# Inverter.net
KiCad netlist of a schematic drawn in Altium Designer
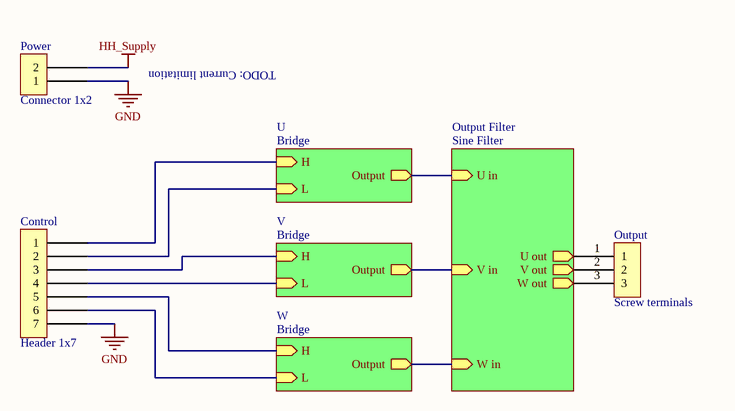
[diagram p0: Inverter.SchDoc]

(export (version "E")
  (design (tool "Eeschema 10.0.6"))
  (components
    (comp (ref "Control")
      (value "Header 1x7")
      (footprint "Header 1x7")
      (libsource (lib "Headers") (part "Header 1x7"))
    )
    (comp (ref "Output")
      (value "Screw terminals")
      (footprint "DG301-5.0-03")
      (libsource (lib "Headers") (part "Header 1x3"))
    )
    (comp (ref "Power")
      (value "Connector 1x2")
      (footprint "DG301-5.0-02")
      (libsource (lib "Headers") (part "Header 2x1"))
    )
  )
  (nets
    (net (code "1") (name "/H") (class "Default")
      (node (ref "Control") (pin "5") (pinfunction "5_5") (pintype "passive"))
    )
    (net (code "2") (name "/H_1") (class "Default")
      (node (ref "Control") (pin "1") (pinfunction "1_1") (pintype "passive"))
    )
    (net (code "3") (name "/H_2") (class "Default")
      (node (ref "Control") (pin "3") (pinfunction "3_3") (pintype "passive"))
    )
    (net (code "4") (name "/L") (class "Default")
      (node (ref "Control") (pin "4") (pinfunction "4_4") (pintype "passive"))
    )
    (net (code "5") (name "/L_1") (class "Default")
      (node (ref "Control") (pin "2") (pinfunction "2_2") (pintype "passive"))
    )
    (net (code "6") (name "/L_2") (class "Default")
      (node (ref "Control") (pin "6") (pinfunction "6_6") (pintype "passive"))
    )
    (net (code "10") (name "/U out") (class "Default")
      (node (ref "Output") (pin "1") (pinfunction "1_1") (pintype "passive"))
    )
    (net (code "11") (name "/V out") (class "Default")
      (node (ref "Output") (pin "2") (pinfunction "2_2") (pintype "passive"))
    )
    (net (code "12") (name "/W out") (class "Default")
      (node (ref "Output") (pin "3") (pinfunction "3_3") (pintype "passive"))
    )
    (net (code "13") (name "GND") (class "Default")
      (node (ref "Control") (pin "7") (pinfunction "7_7") (pintype "passive"))
      (node (ref "Power") (pin "1") (pinfunction "1_1") (pintype "passive"))
    )
    (net (code "14") (name "HH_Supply") (class "Default")
      (node (ref "Power") (pin "2") (pinfunction "2_2") (pintype "passive"))
    )
  )
)
